# DaviShematic.net
KiCad netlist of a schematic drawn in EAGLE
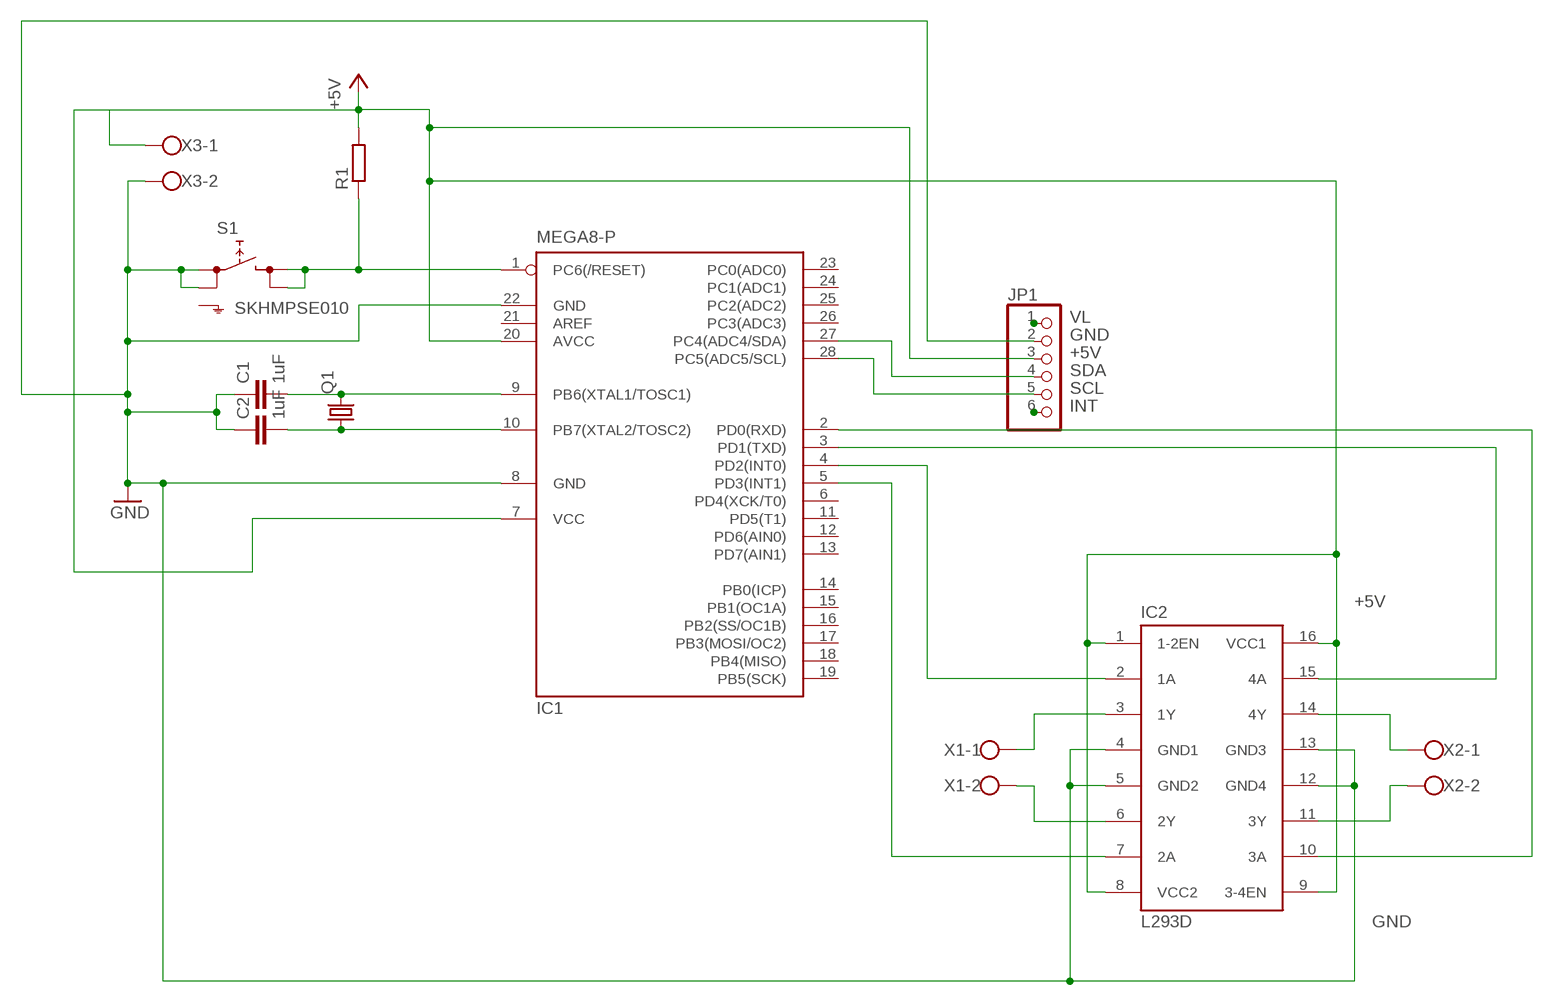
[diagram p0: schematic, sheet 1]

(export (version "E")
  (design (tool "Eeschema 10.0.6"))
  (components
    (comp (ref "C1")
      (value "1uF")
      (footprint "eagle-import:C025-025X050")
      (libsource (lib "eagle-import") (part "C-EU025-025X050"))
    )
    (comp (ref "C2")
      (value "1uF")
      (footprint "eagle-import:C025-025X050")
      (libsource (lib "eagle-import") (part "C-EU025-025X050"))
    )
    (comp (ref "IC1")
      (value "MEGA8-P")
      (footprint "eagle-import:DIL28-3")
      (libsource (lib "eagle-import") (part "MEGA8-P"))
    )
    (comp (ref "IC2")
      (value "L293D")
      (footprint "eagle-import:DIL16")
      (libsource (lib "eagle-import") (part "L293D"))
    )
    (comp (ref "JP1")
      (value "PINHD-1X6")
      (footprint "eagle-import:1X06")
      (libsource (lib "eagle-import") (part "PINHD-1X6"))
    )
    (comp (ref "Q1")
      (value "CRYSTALHC49U-V")
      (footprint "eagle-import:HC49U-V")
      (libsource (lib "eagle-import") (part "CRYSTALHC49U-V"))
    )
    (comp (ref "R1")
      (value "R-EU_0204/7")
      (footprint "eagle-import:0204_7")
      (libsource (lib "eagle-import") (part "R-EU_0204/7"))
    )
    (comp (ref "S1")
      (value "SKHMPSE010")
      (footprint "eagle-import:SKHMPXE010")
      (libsource (lib "eagle-import") (part "SKHMPE010S"))
    )
    (comp (ref "X1")
      (value "W237-102")
      (footprint "eagle-import:W237-102")
      (fields (field (name "MPN") "237-102"))
      (libsource (lib "eagle-import") (part "W237-102"))
    )
    (comp (ref "X2")
      (value "W237-102")
      (footprint "eagle-import:W237-102")
      (fields (field (name "MPN") "237-102"))
      (libsource (lib "eagle-import") (part "W237-102"))
    )
    (comp (ref "X3")
      (value "W237-102")
      (footprint "eagle-import:W237-102")
      (fields (field (name "MPN") "237-102"))
      (libsource (lib "eagle-import") (part "W237-102"))
    )
  )
  (nets
    (net (code "1") (name "+5V") (class "Default")
      (node (ref "IC1") (pin "20") (pinfunction "AVCC_20") (pintype "power_in"))
      (node (ref "IC1") (pin "7") (pinfunction "VCC_7") (pintype "power_in"))
      (node (ref "IC2") (pin "1") (pinfunction "1-2EN_1") (pintype "input"))
      (node (ref "IC2") (pin "16") (pinfunction "VCC1_16") (pintype "power_in"))
      (node (ref "IC2") (pin "8") (pinfunction "VCC2_8") (pintype "power_in"))
      (node (ref "IC2") (pin "9") (pinfunction "3-4EN_9") (pintype "input"))
      (node (ref "JP1") (pin "3") (pinfunction "3_3") (pintype "passive"))
      (node (ref "R1") (pin "2") (pinfunction "2_2") (pintype "passive"))
      (node (ref "X3") (pin "1") (pinfunction "KL_1") (pintype "passive"))
    )
    (net (code "2") (name "/INT") (class "Default")
      (node (ref "JP1") (pin "6") (pinfunction "6_6") (pintype "passive"))
    )
    (net (code "3") (name "/SCL") (class "Default")
      (node (ref "IC1") (pin "28") (pinfunction "PC5(ADC5/SCL)_28") (pintype "bidirectional"))
      (node (ref "JP1") (pin "5") (pinfunction "5_5") (pintype "passive"))
    )
    (net (code "4") (name "/SDA") (class "Default")
      (node (ref "IC1") (pin "27") (pinfunction "PC4(ADC4/SDA)_27") (pintype "bidirectional"))
      (node (ref "JP1") (pin "4") (pinfunction "4_4") (pintype "passive"))
    )
    (net (code "5") (name "/VL") (class "Default")
      (node (ref "JP1") (pin "1") (pinfunction "1_1") (pintype "passive"))
    )
    (net (code "6") (name "GND") (class "Default")
      (node (ref "C1") (pin "1") (pinfunction "1_1") (pintype "passive"))
      (node (ref "C2") (pin "1") (pinfunction "1_1") (pintype "passive"))
      (node (ref "IC1") (pin "22") (pinfunction "GND_22") (pintype "power_in"))
      (node (ref "IC1") (pin "8") (pinfunction "GND_8") (pintype "power_in"))
      (node (ref "IC2") (pin "12") (pinfunction "GND4_12") (pintype "power_in"))
      (node (ref "IC2") (pin "13") (pinfunction "GND3_13") (pintype "power_in"))
      (node (ref "IC2") (pin "4") (pinfunction "GND1_4") (pintype "power_in"))
      (node (ref "IC2") (pin "5") (pinfunction "GND2_5") (pintype "power_in"))
      (node (ref "JP1") (pin "2") (pinfunction "2_2") (pintype "passive"))
      (node (ref "S1") (pin "1") (pinfunction "1.1_1") (pintype "passive"))
      (node (ref "S1") (pin "2") (pinfunction "1.2_2") (pintype "passive"))
      (node (ref "X3") (pin "2") (pinfunction "KL_2") (pintype "passive"))
    )
    (net (code "7") (name "Net-(IC1-PB6(XTAL1{slash}TOSC1))") (class "Default")
      (node (ref "C1") (pin "2") (pinfunction "2_2") (pintype "passive"))
      (node (ref "IC1") (pin "9") (pinfunction "PB6(XTAL1/TOSC1)_9") (pintype "bidirectional"))
      (node (ref "Q1") (pin "2") (pinfunction "2_2") (pintype "passive"))
    )
    (net (code "8") (name "Net-(IC1-PB7(XTAL2{slash}TOSC2))") (class "Default")
      (node (ref "C2") (pin "2") (pinfunction "2_2") (pintype "passive"))
      (node (ref "IC1") (pin "10") (pinfunction "PB7(XTAL2/TOSC2)_10") (pintype "bidirectional"))
      (node (ref "Q1") (pin "1") (pinfunction "1_1") (pintype "passive"))
    )
    (net (code "9") (name "Net-(IC1-PC6({slash}RESET))") (class "Default")
      (node (ref "IC1") (pin "1") (pinfunction "PC6(/RESET)_1") (pintype "bidirectional"))
      (node (ref "R1") (pin "1") (pinfunction "1_1") (pintype "passive"))
      (node (ref "S1") (pin "3") (pinfunction "2.1_3") (pintype "passive"))
      (node (ref "S1") (pin "4") (pinfunction "2.2_4") (pintype "passive"))
    )
    (net (code "10") (name "Net-(IC1-PD0(RXD))") (class "Default")
      (node (ref "IC1") (pin "2") (pinfunction "PD0(RXD)_2") (pintype "bidirectional"))
      (node (ref "IC2") (pin "10") (pinfunction "3A_10") (pintype "input"))
    )
    (net (code "11") (name "Net-(IC1-PD1(TXD))") (class "Default")
      (node (ref "IC1") (pin "3") (pinfunction "PD1(TXD)_3") (pintype "bidirectional"))
      (node (ref "IC2") (pin "15") (pinfunction "4A_15") (pintype "input"))
    )
    (net (code "12") (name "Net-(IC1-PD2(INT0))") (class "Default")
      (node (ref "IC1") (pin "4") (pinfunction "PD2(INT0)_4") (pintype "bidirectional"))
      (node (ref "IC2") (pin "2") (pinfunction "1A_2") (pintype "input"))
    )
    (net (code "13") (name "Net-(IC1-PD3(INT1))") (class "Default")
      (node (ref "IC1") (pin "5") (pinfunction "PD3(INT1)_5") (pintype "bidirectional"))
      (node (ref "IC2") (pin "7") (pinfunction "2A_7") (pintype "input"))
    )
    (net (code "14") (name "Net-(IC2-1Y)") (class "Default")
      (node (ref "IC2") (pin "3") (pinfunction "1Y_3") (pintype "output"))
      (node (ref "X1") (pin "1") (pinfunction "KL_1") (pintype "passive"))
    )
    (net (code "15") (name "Net-(IC2-2Y)") (class "Default")
      (node (ref "IC2") (pin "6") (pinfunction "2Y_6") (pintype "output"))
      (node (ref "X1") (pin "2") (pinfunction "KL_2") (pintype "passive"))
    )
    (net (code "16") (name "Net-(IC2-3Y)") (class "Default")
      (node (ref "IC2") (pin "11") (pinfunction "3Y_11") (pintype "output"))
      (node (ref "X2") (pin "2") (pinfunction "KL_2") (pintype "passive"))
    )
    (net (code "17") (name "Net-(IC2-4Y)") (class "Default")
      (node (ref "IC2") (pin "14") (pinfunction "4Y_14") (pintype "output"))
      (node (ref "X2") (pin "1") (pinfunction "KL_1") (pintype "passive"))
    )
    (net (code "18") (name "unconnected-(IC1-AREF-Pad21)") (class "Default")
      (node (ref "IC1") (pin "21") (pinfunction "AREF_21") (pintype "passive"))
    )
    (net (code "19") (name "unconnected-(IC1-PB0(ICP)-Pad14)") (class "Default")
      (node (ref "IC1") (pin "14") (pinfunction "PB0(ICP)_14") (pintype "bidirectional"))
    )
    (net (code "20") (name "unconnected-(IC1-PB1(OC1A)-Pad15)") (class "Default")
      (node (ref "IC1") (pin "15") (pinfunction "PB1(OC1A)_15") (pintype "bidirectional"))
    )
    (net (code "21") (name "unconnected-(IC1-PB2(SS{slash}OC1B)-Pad16)") (class "Default")
      (node (ref "IC1") (pin "16") (pinfunction "PB2(SS/OC1B)_16") (pintype "bidirectional"))
    )
    (net (code "22") (name "unconnected-(IC1-PB3(MOSI{slash}OC2)-Pad17)") (class "Default")
      (node (ref "IC1") (pin "17") (pinfunction "PB3(MOSI/OC2)_17") (pintype "bidirectional"))
    )
    (net (code "23") (name "unconnected-(IC1-PB4(MISO)-Pad18)") (class "Default")
      (node (ref "IC1") (pin "18") (pinfunction "PB4(MISO)_18") (pintype "bidirectional"))
    )
    (net (code "24") (name "unconnected-(IC1-PB5(SCK)-Pad19)") (class "Default")
      (node (ref "IC1") (pin "19") (pinfunction "PB5(SCK)_19") (pintype "bidirectional"))
    )
    (net (code "25") (name "unconnected-(IC1-PC0(ADC0)-Pad23)") (class "Default")
      (node (ref "IC1") (pin "23") (pinfunction "PC0(ADC0)_23") (pintype "bidirectional"))
    )
    (net (code "26") (name "unconnected-(IC1-PC1(ADC1)-Pad24)") (class "Default")
      (node (ref "IC1") (pin "24") (pinfunction "PC1(ADC1)_24") (pintype "bidirectional"))
    )
    (net (code "27") (name "unconnected-(IC1-PC2(ADC2)-Pad25)") (class "Default")
      (node (ref "IC1") (pin "25") (pinfunction "PC2(ADC2)_25") (pintype "bidirectional"))
    )
    (net (code "28") (name "unconnected-(IC1-PC3(ADC3)-Pad26)") (class "Default")
      (node (ref "IC1") (pin "26") (pinfunction "PC3(ADC3)_26") (pintype "bidirectional"))
    )
    (net (code "29") (name "unconnected-(IC1-PD4(XCK{slash}T0)-Pad6)") (class "Default")
      (node (ref "IC1") (pin "6") (pinfunction "PD4(XCK/T0)_6") (pintype "bidirectional"))
    )
    (net (code "30") (name "unconnected-(IC1-PD5(T1)-Pad11)") (class "Default")
      (node (ref "IC1") (pin "11") (pinfunction "PD5(T1)_11") (pintype "bidirectional"))
    )
    (net (code "31") (name "unconnected-(IC1-PD6(AIN0)-Pad12)") (class "Default")
      (node (ref "IC1") (pin "12") (pinfunction "PD6(AIN0)_12") (pintype "bidirectional"))
    )
    (net (code "32") (name "unconnected-(IC1-PD7(AIN1)-Pad13)") (class "Default")
      (node (ref "IC1") (pin "13") (pinfunction "PD7(AIN1)_13") (pintype "bidirectional"))
    )
    (net (code "33") (name "unconnected-(S1-SH-Pad5)") (class "Default")
      (node (ref "S1") (pin "5") (pinfunction "SH_5") (pintype "passive"))
    )
  )
)
